# RMT_PWR_SCH.net
KiCad netlist of a schematic drawn in Altium Designer
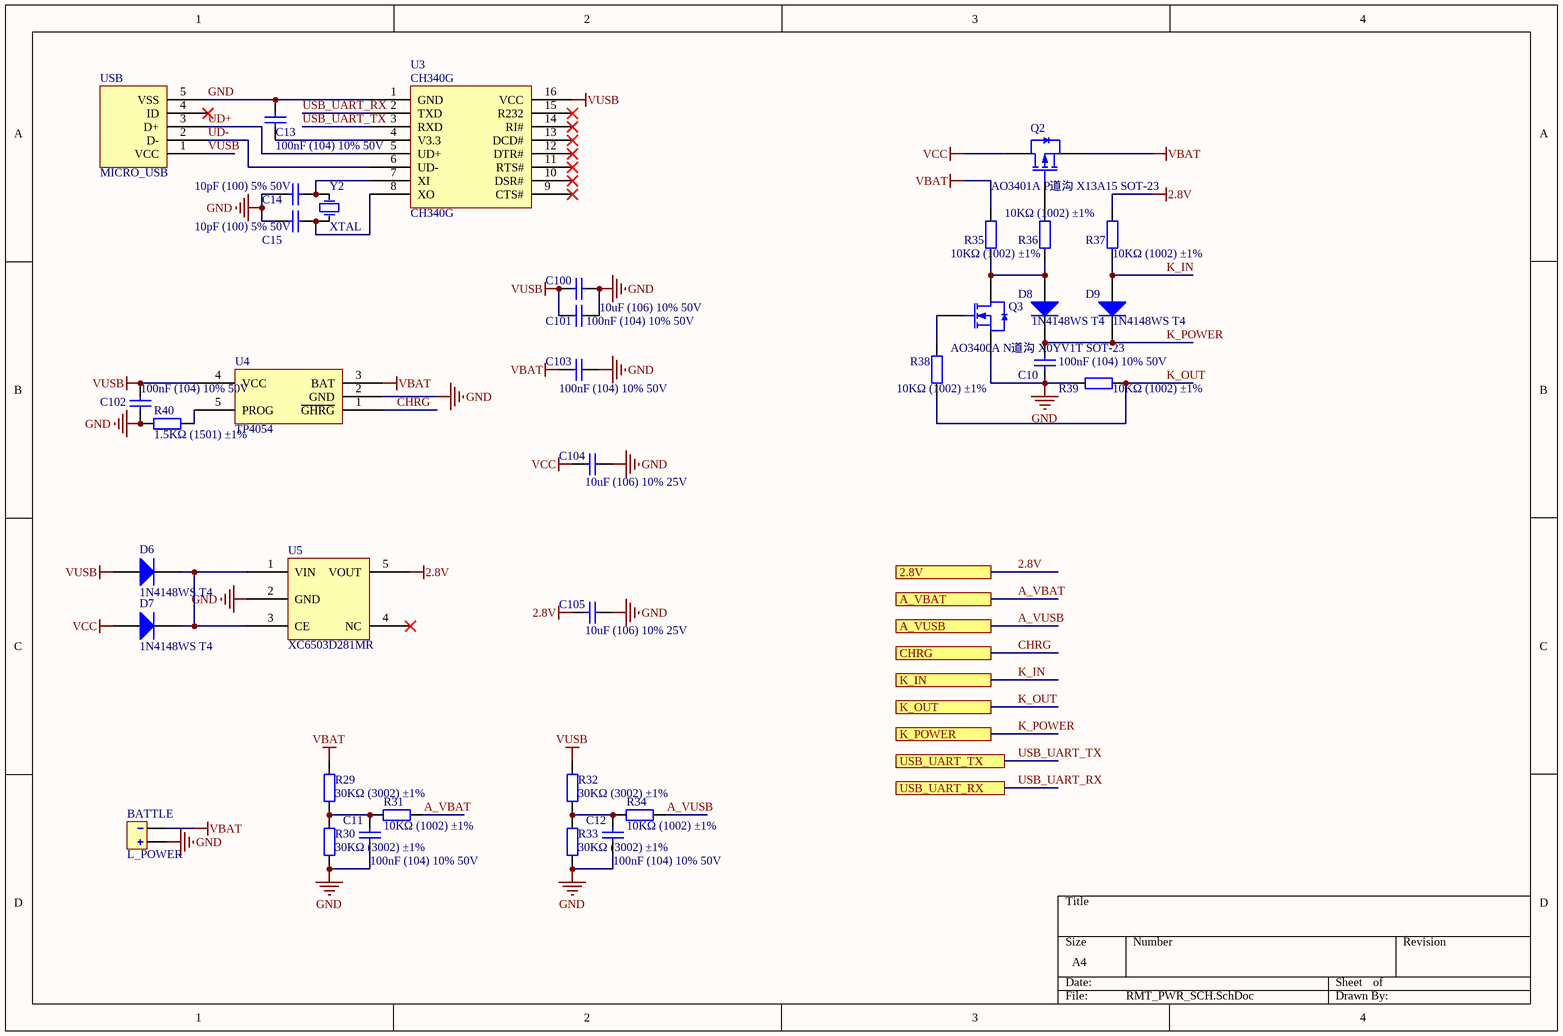
[diagram p0: RMT_PWR_SCH.SchDoc]

(export (version "E")
  (design (tool "Eeschema 10.0.6"))
  (components
    (comp (ref "BATTLE")
      (value "L_POWER")
      (footprint "MOLEX-53398-02")
      (description "电源输入")
      (libsource (lib "Main_Ctr_SchLib") (part "L_POWER"))
    )
    (comp (ref "C10")
      (value "100nF (104) 10% 50V")
      (footprint "0603_C")
      (description "贴片电容")
      (libsource (lib "Miscellaneous Devices LC") (part "0603 100nF (104) 10% 50V"))
    )
    (comp (ref "C11")
      (value "100nF (104) 10% 50V")
      (footprint "0603_C")
      (description "贴片电容")
      (libsource (lib "Miscellaneous Devices LC") (part "0603 100nF (104) 10% 50V"))
    )
    (comp (ref "C12")
      (value "100nF (104) 10% 50V")
      (footprint "0603_C")
      (description "贴片电容")
      (libsource (lib "Miscellaneous Devices LC") (part "0603 100nF (104) 10% 50V"))
    )
    (comp (ref "C13")
      (value "100nF (104) 10% 50V")
      (footprint "0603_C")
      (description "贴片电容")
      (libsource (lib "Miscellaneous Devices LC") (part "0603 100nF (104) 10% 50V"))
    )
    (comp (ref "C14")
      (value "10pF (100) 5% 50V")
      (footprint "0603_C")
      (description "贴片电容")
      (libsource (lib "Miscellaneous Devices LC") (part "0603 10pF (100) 5% 50V"))
    )
    (comp (ref "C15")
      (value "10pF (100) 5% 50V")
      (footprint "0603_C")
      (description "贴片电容")
      (libsource (lib "Miscellaneous Devices LC") (part "0603 10pF (100) 5% 50V"))
    )
    (comp (ref "C100")
      (value "10uF (106) 10% 50V")
      (footprint "1206_C")
      (description "贴片电容")
      (libsource (lib "Miscellaneous Devices LC") (part "1206 10uF (106) 10% 50V"))
    )
    (comp (ref "C101")
      (value "100nF (104) 10% 50V")
      (footprint "0603_C")
      (description "贴片电容")
      (libsource (lib "Miscellaneous Devices LC") (part "0603 100nF (104) 10% 50V"))
    )
    (comp (ref "C102")
      (value "100nF (104) 10% 50V")
      (footprint "0603_C")
      (description "贴片电容")
      (libsource (lib "Miscellaneous Devices LC") (part "0603 100nF (104) 10% 50V"))
    )
    (comp (ref "C103")
      (value "100nF (104) 10% 50V")
      (footprint "0603_C")
      (description "贴片电容")
      (libsource (lib "Miscellaneous Devices LC") (part "0603 100nF (104) 10% 50V"))
    )
    (comp (ref "C104")
      (value "10uF (106) 10% 25V")
      (footprint "0805_C")
      (description "贴片电容")
      (libsource (lib "Miscellaneous Devices LC") (part "0805 10uF (106) 10% 25V"))
    )
    (comp (ref "C105")
      (value "10uF (106) 10% 25V")
      (footprint "0805_C")
      (description "贴片电容")
      (libsource (lib "Miscellaneous Devices LC") (part "0805 10uF (106) 10% 25V"))
    )
    (comp (ref "D6")
      (value "1N4148WS T4")
      (footprint "SOD-323")
      (description "二极管")
      (libsource (lib "Miscellaneous Devices LC") (part "SOD-323 1N4148WS T4"))
    )
    (comp (ref "D7")
      (value "1N4148WS T4")
      (footprint "SOD-323")
      (description "二极管")
      (libsource (lib "Miscellaneous Devices LC") (part "SOD-323 1N4148WS T4"))
    )
    (comp (ref "D8")
      (value "1N4148WS T4")
      (footprint "SOD-323")
      (description "二极管")
      (libsource (lib "Miscellaneous Devices LC") (part "SOD-323 1N4148WS T4"))
    )
    (comp (ref "D9")
      (value "1N4148WS T4")
      (footprint "SOD-323")
      (description "二极管")
      (libsource (lib "Miscellaneous Devices LC") (part "SOD-323 1N4148WS T4"))
    )
    (comp (ref "Q2")
      (value "AO3401A P道沟 X13A15 SOT-23")
      (footprint "SOT-23-3L")
      (description "MOS(场效应管)")
      (libsource (lib "Miscellaneous Devices LC") (part "AO3401A P道沟 X13A15 SOT-23"))
    )
    (comp (ref "Q3")
      (value "AO3400A N道沟 X0YV1T SOT-23")
      (footprint "SOT-23-3L")
      (description "MOS(场效应管)")
      (libsource (lib "Miscellaneous Devices LC") (part "AO3400A N道沟 X0YV1T SOT-23"))
    )
    (comp (ref "R29")
      (value "30KΩ (3002) ±1%")
      (footprint "0603_R")
      (description "贴片电阻")
      (libsource (lib "Miscellaneous Devices LC") (part "0603 30KΩ (3002) 1%"))
    )
    (comp (ref "R30")
      (value "30KΩ (3002) ±1%")
      (footprint "0603_R")
      (description "贴片电阻")
      (libsource (lib "Miscellaneous Devices LC") (part "0603 30KΩ (3002) 1%"))
    )
    (comp (ref "R31")
      (value "10KΩ (1002) ±1%")
      (footprint "0603_R")
      (description "贴片电阻")
      (libsource (lib "Miscellaneous Devices LC") (part "0603 10KΩ (1002) 1%"))
    )
    (comp (ref "R32")
      (value "30KΩ (3002) ±1%")
      (footprint "0603_R")
      (description "贴片电阻")
      (libsource (lib "Miscellaneous Devices LC") (part "0603 30KΩ (3002) 1%"))
    )
    (comp (ref "R33")
      (value "30KΩ (3002) ±1%")
      (footprint "0603_R")
      (description "贴片电阻")
      (libsource (lib "Miscellaneous Devices LC") (part "0603 30KΩ (3002) 1%"))
    )
    (comp (ref "R34")
      (value "10KΩ (1002) ±1%")
      (footprint "0603_R")
      (description "贴片电阻")
      (libsource (lib "Miscellaneous Devices LC") (part "0603 10KΩ (1002) 1%"))
    )
    (comp (ref "R35")
      (value "10KΩ (1002) ±1%")
      (footprint "0603_R")
      (description "贴片电阻")
      (libsource (lib "") (part "0603 10KΩ (1002) 1%_1"))
    )
    (comp (ref "R36")
      (value "10KΩ (1002) ±1%")
      (footprint "0603_R")
      (description "贴片电阻")
      (libsource (lib "") (part "0603 10KΩ (1002) 1%_1"))
    )
    (comp (ref "R37")
      (value "10KΩ (1002) ±1%")
      (footprint "0603_R")
      (description "贴片电阻")
      (libsource (lib "") (part "0603 10KΩ (1002) 1%_1"))
    )
    (comp (ref "R38")
      (value "10KΩ (1002) ±1%")
      (footprint "0603_R")
      (description "贴片电阻")
      (libsource (lib "") (part "0603 10KΩ (1002) 1%_1"))
    )
    (comp (ref "R39")
      (value "10KΩ (1002) ±1%")
      (footprint "0603_R")
      (description "贴片电阻")
      (libsource (lib "Miscellaneous Devices LC") (part "0603 10KΩ (1002) 1%"))
    )
    (comp (ref "R40")
      (value "1.5KΩ (1501) ±1%")
      (footprint "0603_R")
      (description "贴片电阻")
      (libsource (lib "Miscellaneous Devices LC") (part "0603 1.5KΩ (1501) 1%"))
    )
    (comp (ref "U3")
      (value "CH340G")
      (footprint "SOIC-16_150mil")
      (description "USB")
      (libsource (lib "Miscellaneous Devices LC") (part "CH340G_[C14267]"))
    )
    (comp (ref "U4")
      (value "TP4054")
      (footprint "SOT-23-5")
      (description "电池电源管理")
      (libsource (lib "Miscellaneous Devices LC") (part "TP4054_[C32574]"))
    )
    (comp (ref "U5")
      (value "XC6503D281MR")
      (footprint "SOT23-5")
      (description "2.8V 500ma线性稳压器")
      (libsource (lib "Main_Ctr_SchLib") (part "XC6503D281MR"))
    )
    (comp (ref "USB")
      (value "MICRO_USB")
      (footprint "MICRO-USB-B")
      (description "MICRO USB 接口")
      (libsource (lib "Main_Ctr_SchLib") (part "MICRO_USB"))
    )
    (comp (ref "Y2")
      (value "XTAL")
      (footprint "5032")
      (description "无源晶振")
      (libsource (lib "Main_Ctr_SchLib") (part "XTAL"))
    )
  )
  (nets
    (net (code "1") (name "/A_VBAT") (class "Default")
      (node (ref "R31") (pin "2") (pinfunction "2_2") (pintype "passive"))
    )
    (net (code "2") (name "/A_VUSB") (class "Default")
      (node (ref "R34") (pin "2") (pinfunction "2_2") (pintype "passive"))
    )
    (net (code "3") (name "/CHRG") (class "Default")
      (node (ref "U4") (pin "1") (pinfunction "~{GHRG}_1") (pintype "passive"))
    )
    (net (code "4") (name "/K_IN") (class "Default")
      (node (ref "D9") (pin "1") (pinfunction "A_1") (pintype "passive"))
      (node (ref "R37") (pin "1") (pinfunction "1_1") (pintype "passive"))
    )
    (net (code "5") (name "/K_OUT") (class "Default")
      (node (ref "R38") (pin "1") (pinfunction "1_1") (pintype "passive"))
      (node (ref "R39") (pin "2") (pinfunction "2_2") (pintype "passive"))
    )
    (net (code "6") (name "/K_POWER") (class "Default")
      (node (ref "C10") (pin "2") (pinfunction "2_2") (pintype "passive"))
      (node (ref "D8") (pin "2") (pinfunction "K_2") (pintype "passive"))
      (node (ref "D9") (pin "2") (pinfunction "K_2") (pintype "passive"))
    )
    (net (code "7") (name "/UD+") (class "Default")
      (node (ref "U3") (pin "5") (pinfunction "UD+_5") (pintype "passive"))
      (node (ref "USB") (pin "3") (pinfunction "D+_3") (pintype "passive"))
    )
    (net (code "8") (name "/UD-") (class "Default")
      (node (ref "U3") (pin "6") (pinfunction "UD-_6") (pintype "passive"))
      (node (ref "USB") (pin "2") (pinfunction "D-_2") (pintype "passive"))
    )
    (net (code "9") (name "/USB_UART_RX") (class "Default")
      (node (ref "U3") (pin "2") (pinfunction "TXD_2") (pintype "passive"))
    )
    (net (code "10") (name "/USB_UART_TX") (class "Default")
      (node (ref "U3") (pin "3") (pinfunction "RXD_3") (pintype "passive"))
    )
    (net (code "11") (name "2.8V") (class "Default")
      (node (ref "C105") (pin "2") (pinfunction "2_2") (pintype "passive"))
      (node (ref "R37") (pin "2") (pinfunction "2_2") (pintype "passive"))
      (node (ref "U5") (pin "5") (pinfunction "VOUT_5") (pintype "passive"))
    )
    (net (code "12") (name "GND") (class "Default")
      (node (ref "BATTLE") (pin "1") (pinfunction "1_1") (pintype "passive"))
      (node (ref "C10") (pin "1") (pinfunction "1_1") (pintype "passive"))
      (node (ref "C100") (pin "1") (pinfunction "1_1") (pintype "passive"))
      (node (ref "C101") (pin "1") (pinfunction "1_1") (pintype "passive"))
      (node (ref "C102") (pin "1") (pinfunction "1_1") (pintype "passive"))
      (node (ref "C103") (pin "1") (pinfunction "1_1") (pintype "passive"))
      (node (ref "C104") (pin "1") (pinfunction "1_1") (pintype "passive"))
      (node (ref "C105") (pin "1") (pinfunction "1_1") (pintype "passive"))
      (node (ref "C11") (pin "1") (pinfunction "1_1") (pintype "passive"))
      (node (ref "C12") (pin "1") (pinfunction "1_1") (pintype "passive"))
      (node (ref "C13") (pin "2") (pinfunction "2_2") (pintype "passive"))
      (node (ref "C14") (pin "2") (pinfunction "2_2") (pintype "passive"))
      (node (ref "C15") (pin "2") (pinfunction "2_2") (pintype "passive"))
      (node (ref "Q3") (pin "2") (pinfunction "S_2") (pintype "passive"))
      (node (ref "R30") (pin "1") (pinfunction "1_1") (pintype "passive"))
      (node (ref "R33") (pin "1") (pinfunction "1_1") (pintype "passive"))
      (node (ref "R39") (pin "1") (pinfunction "1_1") (pintype "passive"))
      (node (ref "R40") (pin "2") (pinfunction "2_2") (pintype "passive"))
      (node (ref "U3") (pin "1") (pinfunction "GND_1") (pintype "passive"))
      (node (ref "U4") (pin "2") (pinfunction "GND_2") (pintype "passive"))
      (node (ref "U5") (pin "2") (pinfunction "GND_2") (pintype "passive"))
      (node (ref "USB") (pin "5") (pinfunction "VSS_5") (pintype "passive"))
    )
    (net (code "13") (name "Net-(C11-Pad2)") (class "Default")
      (node (ref "C11") (pin "2") (pinfunction "2_2") (pintype "passive"))
      (node (ref "R29") (pin "1") (pinfunction "1_1") (pintype "passive"))
      (node (ref "R30") (pin "2") (pinfunction "2_2") (pintype "passive"))
      (node (ref "R31") (pin "1") (pinfunction "1_1") (pintype "passive"))
    )
    (net (code "14") (name "Net-(C12-Pad2)") (class "Default")
      (node (ref "C12") (pin "2") (pinfunction "2_2") (pintype "passive"))
      (node (ref "R32") (pin "1") (pinfunction "1_1") (pintype "passive"))
      (node (ref "R33") (pin "2") (pinfunction "2_2") (pintype "passive"))
      (node (ref "R34") (pin "1") (pinfunction "1_1") (pintype "passive"))
    )
    (net (code "15") (name "Net-(D6-K)") (class "Default")
      (node (ref "D6") (pin "2") (pinfunction "K_2") (pintype "passive"))
      (node (ref "D7") (pin "2") (pinfunction "K_2") (pintype "passive"))
      (node (ref "U5") (pin "1") (pinfunction "VIN_1") (pintype "passive"))
      (node (ref "U5") (pin "3") (pinfunction "CE_3") (pintype "passive"))
    )
    (net (code "16") (name "Net-(D8-A)") (class "Default")
      (node (ref "D8") (pin "1") (pinfunction "A_1") (pintype "passive"))
      (node (ref "Q3") (pin "3") (pinfunction "D_3") (pintype "passive"))
      (node (ref "R35") (pin "1") (pinfunction "1_1") (pintype "passive"))
      (node (ref "R36") (pin "1") (pinfunction "1_1") (pintype "passive"))
    )
    (net (code "17") (name "Net-(Q2-G)") (class "Default")
      (node (ref "Q2") (pin "1") (pinfunction "G_1") (pintype "passive"))
      (node (ref "R36") (pin "2") (pinfunction "2_2") (pintype "passive"))
    )
    (net (code "18") (name "Net-(Q3-G)") (class "Default")
      (node (ref "Q3") (pin "1") (pinfunction "G_1") (pintype "passive"))
      (node (ref "R38") (pin "2") (pinfunction "2_2") (pintype "passive"))
    )
    (net (code "19") (name "Net-(U3-V3.3)") (class "Default")
      (node (ref "C13") (pin "1") (pinfunction "1_1") (pintype "passive"))
      (node (ref "U3") (pin "4") (pinfunction "V3.3_4") (pintype "passive"))
    )
    (net (code "20") (name "Net-(U3-XI)") (class "Default")
      (node (ref "C14") (pin "1") (pinfunction "1_1") (pintype "passive"))
      (node (ref "U3") (pin "7") (pinfunction "XI_7") (pintype "passive"))
      (node (ref "Y2") (pin "1") (pinfunction "OSC1_1") (pintype "passive"))
    )
    (net (code "21") (name "Net-(U3-XO)") (class "Default")
      (node (ref "C15") (pin "1") (pinfunction "1_1") (pintype "passive"))
      (node (ref "U3") (pin "8") (pinfunction "XO_8") (pintype "passive"))
      (node (ref "Y2") (pin "2") (pinfunction "OSC2_2") (pintype "passive"))
    )
    (net (code "22") (name "Net-(U4-PROG)") (class "Default")
      (node (ref "R40") (pin "1") (pinfunction "1_1") (pintype "passive"))
      (node (ref "U4") (pin "5") (pinfunction "PROG_5") (pintype "passive"))
    )
    (net (code "23") (name "VBAT") (class "Default")
      (node (ref "BATTLE") (pin "2") (pinfunction "2_2") (pintype "passive"))
      (node (ref "C103") (pin "2") (pinfunction "2_2") (pintype "passive"))
      (node (ref "Q2") (pin "2") (pinfunction "S_2") (pintype "passive"))
      (node (ref "R29") (pin "2") (pinfunction "2_2") (pintype "passive"))
      (node (ref "R35") (pin "2") (pinfunction "2_2") (pintype "passive"))
      (node (ref "U4") (pin "3") (pinfunction "BAT_3") (pintype "passive"))
    )
    (net (code "24") (name "VCC") (class "Default")
      (node (ref "C104") (pin "2") (pinfunction "2_2") (pintype "passive"))
      (node (ref "D7") (pin "1") (pinfunction "A_1") (pintype "passive"))
      (node (ref "Q2") (pin "3") (pinfunction "D_3") (pintype "passive"))
    )
    (net (code "25") (name "VUSB") (class "Default")
      (node (ref "C100") (pin "2") (pinfunction "2_2") (pintype "passive"))
      (node (ref "C101") (pin "2") (pinfunction "2_2") (pintype "passive"))
      (node (ref "C102") (pin "2") (pinfunction "2_2") (pintype "passive"))
      (node (ref "D6") (pin "1") (pinfunction "A_1") (pintype "passive"))
      (node (ref "R32") (pin "2") (pinfunction "2_2") (pintype "passive"))
      (node (ref "U3") (pin "16") (pinfunction "VCC_16") (pintype "passive"))
      (node (ref "U4") (pin "4") (pinfunction "VCC_4") (pintype "passive"))
      (node (ref "USB") (pin "1") (pinfunction "VCC_1") (pintype "passive"))
    )
    (net (code "26") (name "unconnected-(U3-CTS#-Pad9)") (class "Default")
      (node (ref "U3") (pin "9") (pinfunction "CTS#_9") (pintype "passive+no_connect"))
    )
    (net (code "27") (name "unconnected-(U3-DCD#-Pad13)") (class "Default")
      (node (ref "U3") (pin "13") (pinfunction "DCD#_13") (pintype "passive+no_connect"))
    )
    (net (code "28") (name "unconnected-(U3-DSR#-Pad10)") (class "Default")
      (node (ref "U3") (pin "10") (pinfunction "DSR#_10") (pintype "passive+no_connect"))
    )
    (net (code "29") (name "unconnected-(U3-DTR#-Pad12)") (class "Default")
      (node (ref "U3") (pin "12") (pinfunction "DTR#_12") (pintype "passive+no_connect"))
    )
    (net (code "30") (name "unconnected-(U3-R232-Pad15)") (class "Default")
      (node (ref "U3") (pin "15") (pinfunction "R232_15") (pintype "passive+no_connect"))
    )
    (net (code "31") (name "unconnected-(U3-RI#-Pad14)") (class "Default")
      (node (ref "U3") (pin "14") (pinfunction "RI#_14") (pintype "passive+no_connect"))
    )
    (net (code "32") (name "unconnected-(U3-RTS#-Pad11)") (class "Default")
      (node (ref "U3") (pin "11") (pinfunction "RTS#_11") (pintype "passive+no_connect"))
    )
    (net (code "33") (name "unconnected-(U5-NC-Pad4)") (class "Default")
      (node (ref "U5") (pin "4") (pinfunction "NC_4") (pintype "passive+no_connect"))
    )
    (net (code "34") (name "unconnected-(USB-ID-Pad4)") (class "Default")
      (node (ref "USB") (pin "4") (pinfunction "ID_4") (pintype "passive+no_connect"))
    )
  )
)
